# AUX_power_board.net
KiCad netlist of a schematic drawn in EAGLE
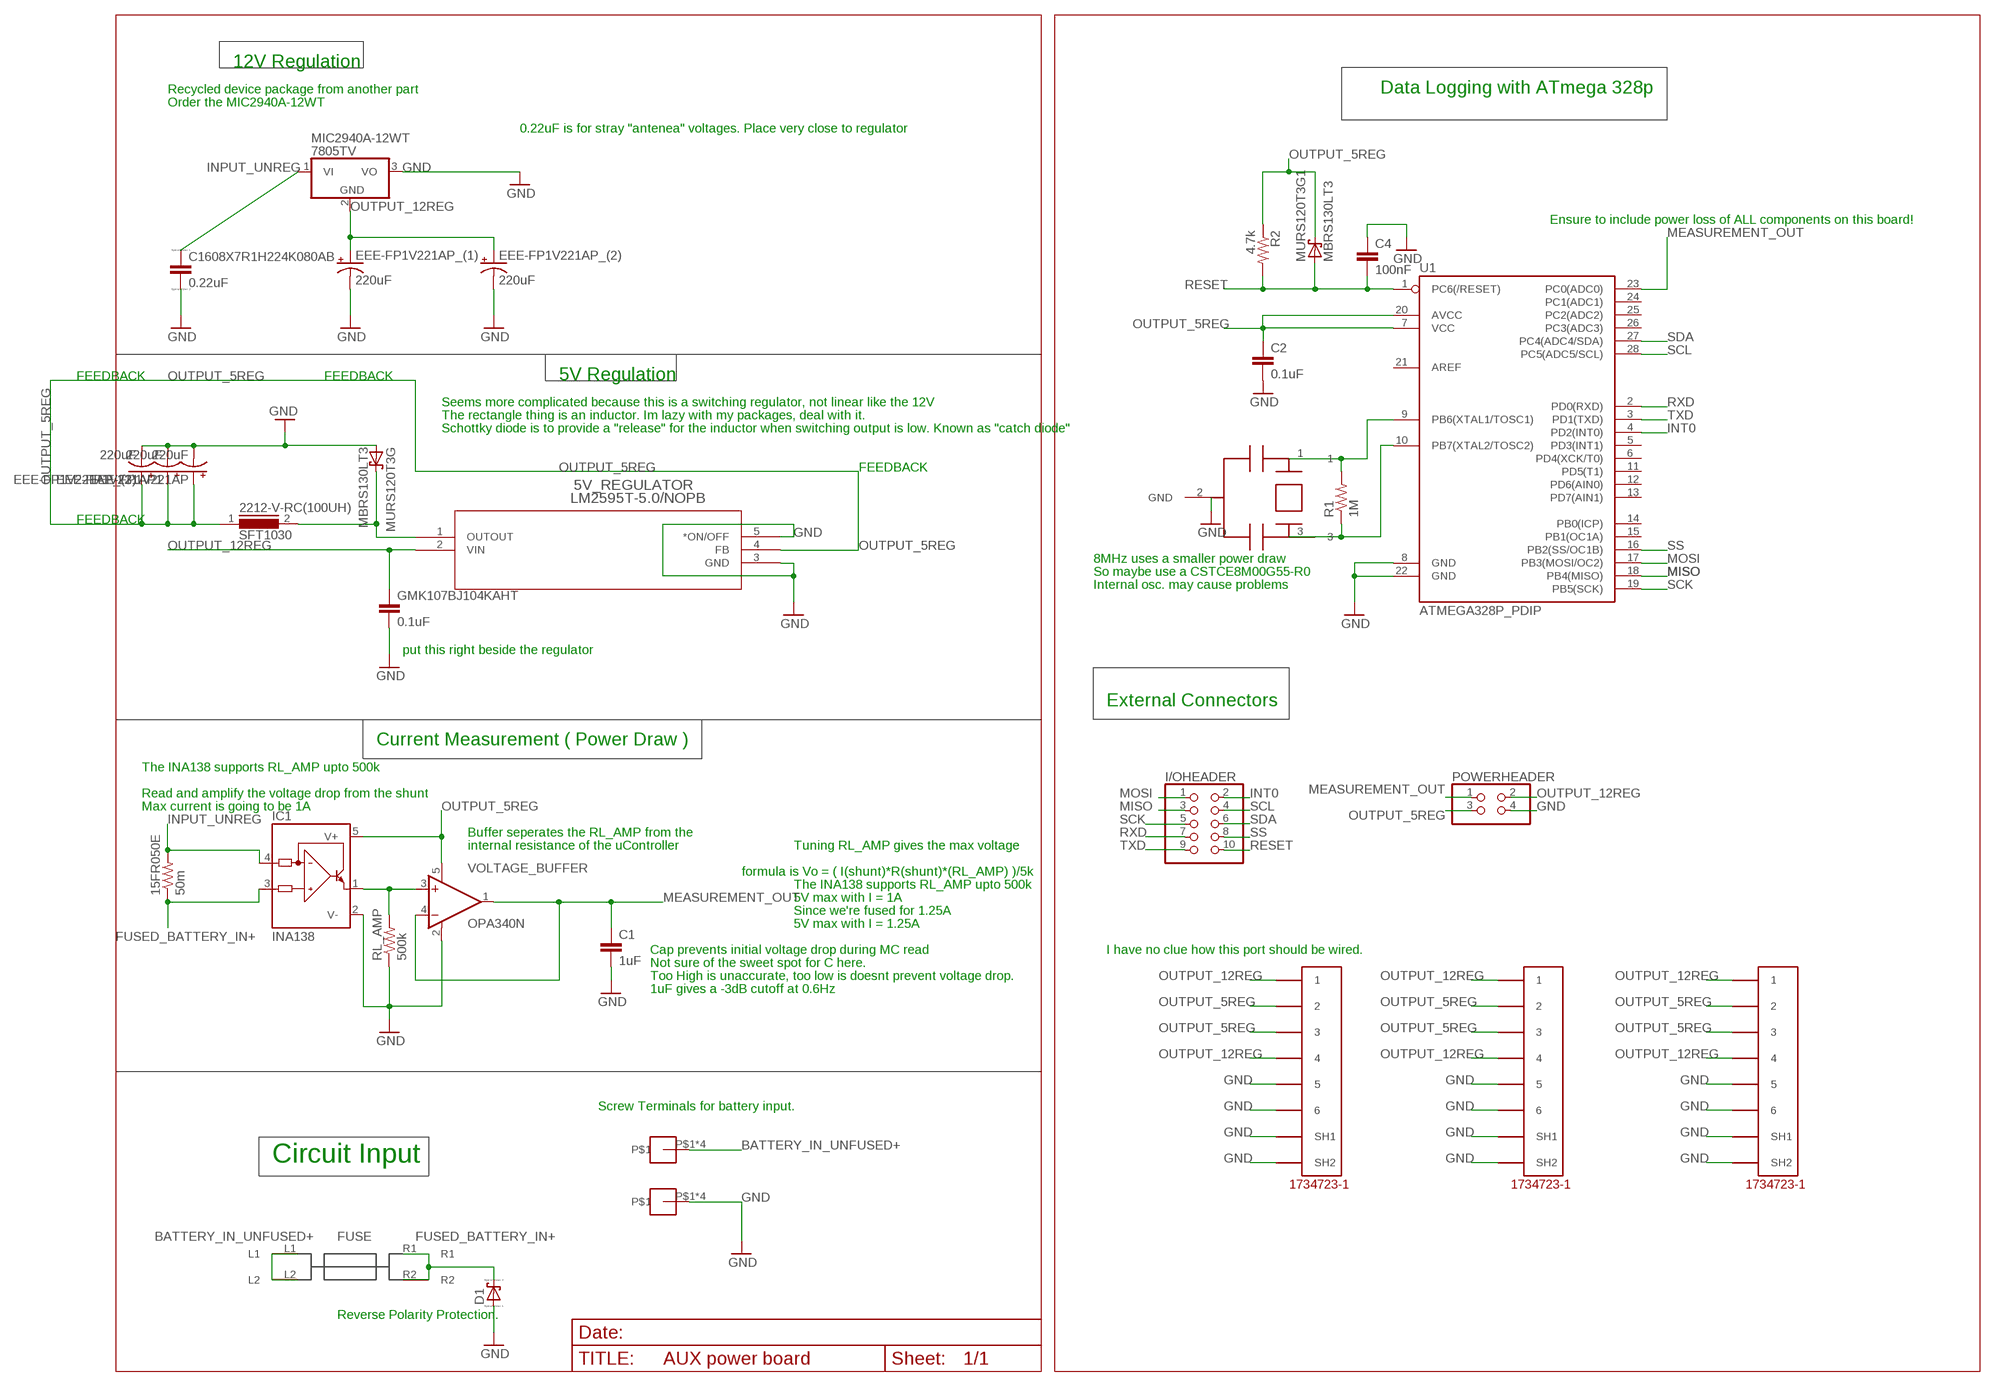
[diagram p0: schematic, sheet 1]

(export (version "E")
  (design (tool "Eeschema 10.0.6"))
  (components
    (comp (ref "5V_REGULATOR")
      (value "LM2595T-5.0/NOPB")
      (footprint "eagle-import:T05D")
      (fields
        (field (name "MANUFACTURER_PART_NUMBER") "LM2595T50")
        (field (name "COPYRIGHT") "Copyright C 2015 Accelerated Designs. All rights reserved")
      )
      (libsource (lib "eagle-import") (part "LM2595T-5.0/NOPB"))
    )
    (comp (ref "15FR050E")
      (value "50m")
      (footprint "eagle-import:0617_22")
      (libsource (lib "eagle-import") (part "resistor_R-US_0617/22"))
    )
    (comp (ref "2212-V-RC(100UH)")
      (value "SFT1030")
      (footprint "eagle-import:SFT1030")
      (libsource (lib "eagle-import") (part "SFT1030"))
    )
    (comp (ref "C1")
      (value "1uF")
      (footprint "eagle-import:C0603")
      (libsource (lib "eagle-import") (part "resistor_C-EUC0603"))
    )
    (comp (ref "C2")
      (value "0.1uF")
      (footprint "eagle-import:C0603")
      (libsource (lib "eagle-import") (part "resistor_C-EUC0603"))
    )
    (comp (ref "C4")
      (value "100nF")
      (footprint "eagle-import:C0603")
      (libsource (lib "eagle-import") (part "C-EUC0603"))
    )
    (comp (ref "C1608X7R1H224K080AB")
      (value "0.22uF")
      (footprint "eagle-import:C0603")
      (libsource (lib "eagle-import") (part "CC0603"))
    )
    (comp (ref "D1")
      (value "SCHOTTKY-DIODESMC")
      (footprint "eagle-import:DIODE_SMC")
      (libsource (lib "eagle-import") (part "SCHOTTKY-DIODESMC"))
    )
    (comp (ref "EEE-FP1V221AP")
      (value "220uF")
      (footprint "eagle-import:175TMP-0808")
      (libsource (lib "eagle-import") (part "CPOL-US175TMP-0808"))
    )
    (comp (ref "EEE-FP1V221AP1")
      (value "220uF")
      (footprint "eagle-import:175TMP-0808")
      (libsource (lib "eagle-import") (part "CPOL-US175TMP-0808"))
    )
    (comp (ref "EEE-FP1V221AP_(1)")
      (value "220uF")
      (footprint "eagle-import:175TMP-0808")
      (libsource (lib "eagle-import") (part "CPOL-US175TMP-0808"))
    )
    (comp (ref "EEE-FP1V221AP_(2)")
      (value "220uF")
      (footprint "eagle-import:175TMP-0808")
      (libsource (lib "eagle-import") (part "CPOL-US175TMP-0808"))
    )
    (comp (ref "EEE-FP1V221AP_(3)")
      (value "220uF")
      (footprint "eagle-import:175TMP-0808")
      (libsource (lib "eagle-import") (part "CPOL-US175TMP-0808"))
    )
    (comp (ref "GMK107BJ104KAHT")
      (value "0.1uF")
      (footprint "eagle-import:C0603")
      (libsource (lib "eagle-import") (part "C-EUC0603"))
    )
    (comp (ref "I/OHEADER")
      (value "PINHD-2X5")
      (footprint "eagle-import:2X05")
      (libsource (lib "eagle-import") (part "PINHD-2X5"))
    )
    (comp (ref "IC1")
      (value "INA138")
      (footprint "eagle-import:SOT23-5")
      (fields (field (name "MF") "TEXAS INSTRUMENTS") (field (name "MPN") "INA138NA/250"))
      (libsource (lib "eagle-import") (part "INA138"))
    )
    (comp (ref "MIC2940A-12WT")
      (value "7805TV")
      (footprint "eagle-import:TO220V")
      (libsource (lib "eagle-import") (part "78TV05"))
    )
    (comp (ref "MINIBLADE")
      (value "3568")
      (footprint "eagle-import:3568")
      (libsource (lib "eagle-import") (part "3568"))
    )
    (comp (ref "MURS120T3G")
      (value "MBRS130LT3")
      (footprint "eagle-import:SMB")
      (libsource (lib "eagle-import") (part "MBRS130LT3"))
    )
    (comp (ref "MURS120T3G1")
      (value "MBRS130LT3")
      (footprint "eagle-import:SMB")
      (libsource (lib "eagle-import") (part "MBRS130LT3"))
    )
    (comp (ref "POWERHEADER")
      (value "PINHD-2X2")
      (footprint "eagle-import:2X02")
      (libsource (lib "eagle-import") (part "PINHD-2X2"))
    )
    (comp (ref "R1")
      (value "1M")
      (footprint "eagle-import:R0603")
      (libsource (lib "eagle-import") (part "R-US_R0603"))
    )
    (comp (ref "R2")
      (value "4.7k")
      (footprint "eagle-import:R0603")
      (libsource (lib "eagle-import") (part "resistor_R-US_R0603"))
    )
    (comp (ref "RL_AMP")
      (value "500k")
      (footprint "eagle-import:R0603")
      (libsource (lib "eagle-import") (part "resistor_R-US_R0603"))
    )
    (comp (ref "U$1")
      (value "CSTCE16M0V53-R0")
      (footprint "eagle-import:RESONATOR")
      (libsource (lib "eagle-import") (part "CSTCE16M0V53-R0"))
    )
    (comp (ref "U$3")
      (value "5555140-6")
      (footprint "eagle-import:1734723-1_RJ11")
      (libsource (lib "eagle-import") (part "5555140-6"))
    )
    (comp (ref "U$4")
      (value "5555140-6")
      (footprint "eagle-import:1734723-1_RJ11")
      (libsource (lib "eagle-import") (part "5555140-6"))
    )
    (comp (ref "U$5")
      (value "5555140-6")
      (footprint "eagle-import:1734723-1_RJ11")
      (libsource (lib "eagle-import") (part "5555140-6"))
    )
    (comp (ref "U$6")
      (value "SCREW-8191")
      (footprint "eagle-import:SCREW-8191")
      (libsource (lib "eagle-import") (part "SCREW-8191"))
    )
    (comp (ref "U$7")
      (value "SCREW-8191")
      (footprint "eagle-import:SCREW-8191")
      (libsource (lib "eagle-import") (part "SCREW-8191"))
    )
    (comp (ref "U1")
      (value "ATMEGA328P_PDIP")
      (footprint "eagle-import:DIL28-3")
      (libsource (lib "eagle-import") (part "ATMEGA328P_PDIP"))
    )
    (comp (ref "VOLTAGE_BUFFER")
      (value "OPA340N")
      (footprint "eagle-import:SOT23-5")
      (fields (field (name "MPN") "OPA340NA/3KG4"))
      (libsource (lib "eagle-import") (part "OPA340N"))
    )
  )
  (nets
    (net (code "1") (name "/BATTERY_IN_UNFUSED+") (class "Default")
      (node (ref "MINIBLADE") (pin "L1") (pinfunction "L1_L1") (pintype "bidirectional"))
      (node (ref "MINIBLADE") (pin "L2") (pinfunction "L2_L2") (pintype "bidirectional"))
      (node (ref "U$6") (pin "P$1") (pinfunction "P$1_P$1") (pintype "bidirectional"))
      (node (ref "U$6") (pin "P$2") (pinfunction "P$1_P$2") (pintype "bidirectional"))
      (node (ref "U$6") (pin "P$3") (pinfunction "P$1_P$3") (pintype "bidirectional"))
      (node (ref "U$6") (pin "P$4") (pinfunction "P$1_P$4") (pintype "bidirectional"))
    )
    (net (code "2") (name "/FUSED_BATTERY_IN+") (class "Default")
      (node (ref "15FR050E") (pin "1") (pinfunction "1_1") (pintype "passive"))
      (node (ref "D1") (pin "C") (pinfunction "A_C") (pintype "passive"))
      (node (ref "IC1") (pin "3") (pinfunction "IN+_3") (pintype "input"))
      (node (ref "MINIBLADE") (pin "R1") (pinfunction "R1_R1") (pintype "bidirectional"))
      (node (ref "MINIBLADE") (pin "R2") (pinfunction "R2_R2") (pintype "bidirectional"))
    )
    (net (code "3") (name "/INPUT_UNREG") (class "Default")
      (node (ref "15FR050E") (pin "2") (pinfunction "2_2") (pintype "passive"))
      (node (ref "C1608X7R1H224K080AB") (pin "1") (pinfunction "1_1") (pintype "passive"))
      (node (ref "IC1") (pin "4") (pinfunction "IN-_4") (pintype "input"))
      (node (ref "MIC2940A-12WT") (pin "1") (pinfunction "VI_1") (pintype "input"))
    )
    (net (code "4") (name "/INT0") (class "Default")
      (node (ref "I/OHEADER") (pin "2") (pinfunction "2_2") (pintype "passive"))
      (node (ref "U1") (pin "4") (pinfunction "PD2(INT0)_4") (pintype "bidirectional"))
    )
    (net (code "5") (name "/MEASUREMENT_OUT") (class "Default")
      (node (ref "C1") (pin "1") (pinfunction "1_1") (pintype "passive"))
      (node (ref "POWERHEADER") (pin "1") (pinfunction "1_1") (pintype "passive"))
      (node (ref "U1") (pin "23") (pinfunction "PC0(ADC0)_23") (pintype "bidirectional"))
      (node (ref "VOLTAGE_BUFFER") (pin "1") (pinfunction "OUT_1") (pintype "output"))
      (node (ref "VOLTAGE_BUFFER") (pin "4") (pinfunction "-IN_4") (pintype "input"))
    )
    (net (code "6") (name "/MISO") (class "Default")
      (node (ref "I/OHEADER") (pin "3") (pinfunction "3_3") (pintype "passive"))
      (node (ref "U1") (pin "18") (pinfunction "PB4(MISO)_18") (pintype "bidirectional"))
    )
    (net (code "7") (name "/MOSI") (class "Default")
      (node (ref "I/OHEADER") (pin "1") (pinfunction "1_1") (pintype "passive"))
      (node (ref "U1") (pin "17") (pinfunction "PB3(MOSI/OC2)_17") (pintype "bidirectional"))
    )
    (net (code "8") (name "/OUTPUT_5REG") (class "Default")
      (node (ref "2212-V-RC(100UH)") (pin "1") (pinfunction "1_1") (pintype "passive"))
      (node (ref "5V_REGULATOR") (pin "4") (pinfunction "FB_4") (pintype "passive"))
      (node (ref "C2") (pin "1") (pinfunction "1_1") (pintype "passive"))
      (node (ref "EEE-FP1V221AP") (pin "+") (pinfunction "+_+") (pintype "passive"))
      (node (ref "EEE-FP1V221AP1") (pin "+") (pinfunction "+_+") (pintype "passive"))
      (node (ref "EEE-FP1V221AP_(3)") (pin "+") (pinfunction "+_+") (pintype "passive"))
      (node (ref "IC1") (pin "5") (pinfunction "V+_5") (pintype "power_in"))
      (node (ref "MURS120T3G1") (pin "C") (pinfunction "C_C") (pintype "passive"))
      (node (ref "POWERHEADER") (pin "3") (pinfunction "3_3") (pintype "passive"))
      (node (ref "R2") (pin "1") (pinfunction "1_1") (pintype "passive"))
      (node (ref "U$3") (pin "2") (pinfunction "2_2") (pintype "bidirectional"))
      (node (ref "U$3") (pin "3") (pinfunction "3_3") (pintype "bidirectional"))
      (node (ref "U$4") (pin "2") (pinfunction "2_2") (pintype "bidirectional"))
      (node (ref "U$4") (pin "3") (pinfunction "3_3") (pintype "bidirectional"))
      (node (ref "U$5") (pin "2") (pinfunction "2_2") (pintype "bidirectional"))
      (node (ref "U$5") (pin "3") (pinfunction "3_3") (pintype "bidirectional"))
      (node (ref "U1") (pin "20") (pinfunction "AVCC_20") (pintype "bidirectional"))
      (node (ref "U1") (pin "7") (pinfunction "VCC_7") (pintype "bidirectional"))
      (node (ref "VOLTAGE_BUFFER") (pin "5") (pinfunction "V+_5") (pintype "power_in"))
    )
    (net (code "9") (name "/OUTPUT_12REG") (class "Default")
      (node (ref "5V_REGULATOR") (pin "2") (pinfunction "VIN_2") (pintype "input"))
      (node (ref "EEE-FP1V221AP_(1)") (pin "+") (pinfunction "+_+") (pintype "passive"))
      (node (ref "EEE-FP1V221AP_(2)") (pin "+") (pinfunction "+_+") (pintype "passive"))
      (node (ref "GMK107BJ104KAHT") (pin "1") (pinfunction "1_1") (pintype "passive"))
      (node (ref "MIC2940A-12WT") (pin "2") (pinfunction "GND_2") (pintype "passive"))
      (node (ref "POWERHEADER") (pin "2") (pinfunction "2_2") (pintype "passive"))
      (node (ref "U$3") (pin "1") (pinfunction "1_1") (pintype "bidirectional"))
      (node (ref "U$3") (pin "4") (pinfunction "4_4") (pintype "bidirectional"))
      (node (ref "U$4") (pin "1") (pinfunction "1_1") (pintype "bidirectional"))
      (node (ref "U$4") (pin "4") (pinfunction "4_4") (pintype "bidirectional"))
      (node (ref "U$5") (pin "1") (pinfunction "1_1") (pintype "bidirectional"))
      (node (ref "U$5") (pin "4") (pinfunction "4_4") (pintype "bidirectional"))
    )
    (net (code "10") (name "/RESET") (class "Default")
      (node (ref "C4") (pin "2") (pinfunction "2_2") (pintype "passive"))
      (node (ref "I/OHEADER") (pin "10") (pinfunction "10_10") (pintype "passive"))
      (node (ref "MURS120T3G1") (pin "A") (pinfunction "A_A") (pintype "passive"))
      (node (ref "R2") (pin "2") (pinfunction "2_2") (pintype "passive"))
      (node (ref "U1") (pin "1") (pinfunction "PC6(/RESET)_1") (pintype "bidirectional"))
    )
    (net (code "11") (name "/RXD") (class "Default")
      (node (ref "I/OHEADER") (pin "7") (pinfunction "7_7") (pintype "passive"))
      (node (ref "U1") (pin "2") (pinfunction "PD0(RXD)_2") (pintype "bidirectional"))
    )
    (net (code "12") (name "/SCK") (class "Default")
      (node (ref "I/OHEADER") (pin "5") (pinfunction "5_5") (pintype "passive"))
      (node (ref "U1") (pin "19") (pinfunction "PB5(SCK)_19") (pintype "bidirectional"))
    )
    (net (code "13") (name "/SCL") (class "Default")
      (node (ref "I/OHEADER") (pin "4") (pinfunction "4_4") (pintype "passive"))
      (node (ref "U1") (pin "28") (pinfunction "PC5(ADC5/SCL)_28") (pintype "bidirectional"))
    )
    (net (code "14") (name "/SDA") (class "Default")
      (node (ref "I/OHEADER") (pin "6") (pinfunction "6_6") (pintype "passive"))
      (node (ref "U1") (pin "27") (pinfunction "PC4(ADC4/SDA)_27") (pintype "bidirectional"))
    )
    (net (code "15") (name "/SS") (class "Default")
      (node (ref "I/OHEADER") (pin "8") (pinfunction "8_8") (pintype "passive"))
      (node (ref "U1") (pin "16") (pinfunction "PB2(SS/OC1B)_16") (pintype "bidirectional"))
    )
    (net (code "16") (name "/TXD") (class "Default")
      (node (ref "I/OHEADER") (pin "9") (pinfunction "9_9") (pintype "passive"))
      (node (ref "U1") (pin "3") (pinfunction "PD1(TXD)_3") (pintype "bidirectional"))
    )
    (net (code "17") (name "GND") (class "Default")
      (node (ref "5V_REGULATOR") (pin "3") (pinfunction "GND_3") (pintype "passive"))
      (node (ref "5V_REGULATOR") (pin "5") (pinfunction "*ON/OFF_5") (pintype "passive"))
      (node (ref "C1") (pin "2") (pinfunction "2_2") (pintype "passive"))
      (node (ref "C1608X7R1H224K080AB") (pin "2") (pinfunction "2_2") (pintype "passive"))
      (node (ref "C2") (pin "2") (pinfunction "2_2") (pintype "passive"))
      (node (ref "C4") (pin "1") (pinfunction "1_1") (pintype "passive"))
      (node (ref "D1") (pin "A") (pinfunction "C_A") (pintype "passive"))
      (node (ref "EEE-FP1V221AP") (pin "-") (pinfunction "-_-") (pintype "passive"))
      (node (ref "EEE-FP1V221AP1") (pin "-") (pinfunction "-_-") (pintype "passive"))
      (node (ref "EEE-FP1V221AP_(1)") (pin "-") (pinfunction "-_-") (pintype "passive"))
      (node (ref "EEE-FP1V221AP_(2)") (pin "-") (pinfunction "-_-") (pintype "passive"))
      (node (ref "EEE-FP1V221AP_(3)") (pin "-") (pinfunction "-_-") (pintype "passive"))
      (node (ref "GMK107BJ104KAHT") (pin "2") (pinfunction "2_2") (pintype "passive"))
      (node (ref "IC1") (pin "2") (pinfunction "V-_2") (pintype "power_in"))
      (node (ref "MIC2940A-12WT") (pin "3") (pinfunction "VO_3") (pintype "passive"))
      (node (ref "MURS120T3G") (pin "A") (pinfunction "A_A") (pintype "passive"))
      (node (ref "POWERHEADER") (pin "4") (pinfunction "4_4") (pintype "passive"))
      (node (ref "RL_AMP") (pin "1") (pinfunction "1_1") (pintype "passive"))
      (node (ref "U$1") (pin "2") (pinfunction "GND_2") (pintype "bidirectional"))
      (node (ref "U$3") (pin "5") (pinfunction "5_5") (pintype "bidirectional"))
      (node (ref "U$3") (pin "6") (pinfunction "6_6") (pintype "bidirectional"))
      (node (ref "U$3") (pin "SH1") (pinfunction "SH1_SH1") (pintype "bidirectional"))
      (node (ref "U$3") (pin "SH2") (pinfunction "SH2_SH2") (pintype "bidirectional"))
      (node (ref "U$4") (pin "5") (pinfunction "5_5") (pintype "bidirectional"))
      (node (ref "U$4") (pin "6") (pinfunction "6_6") (pintype "bidirectional"))
      (node (ref "U$4") (pin "SH1") (pinfunction "SH1_SH1") (pintype "bidirectional"))
      (node (ref "U$4") (pin "SH2") (pinfunction "SH2_SH2") (pintype "bidirectional"))
      (node (ref "U$5") (pin "5") (pinfunction "5_5") (pintype "bidirectional"))
      (node (ref "U$5") (pin "6") (pinfunction "6_6") (pintype "bidirectional"))
      (node (ref "U$5") (pin "SH1") (pinfunction "SH1_SH1") (pintype "bidirectional"))
      (node (ref "U$5") (pin "SH2") (pinfunction "SH2_SH2") (pintype "bidirectional"))
      (node (ref "U$7") (pin "P$1") (pinfunction "P$1_P$1") (pintype "bidirectional"))
      (node (ref "U$7") (pin "P$2") (pinfunction "P$1_P$2") (pintype "bidirectional"))
      (node (ref "U$7") (pin "P$3") (pinfunction "P$1_P$3") (pintype "bidirectional"))
      (node (ref "U$7") (pin "P$4") (pinfunction "P$1_P$4") (pintype "bidirectional"))
      (node (ref "U1") (pin "22") (pinfunction "GND_22") (pintype "bidirectional"))
      (node (ref "U1") (pin "8") (pinfunction "GND_8") (pintype "bidirectional"))
      (node (ref "VOLTAGE_BUFFER") (pin "2") (pinfunction "V-_2") (pintype "power_in"))
    )
    (net (code "18") (name "Net-(5V_REGULATOR-OUTOUT)") (class "Default")
      (node (ref "2212-V-RC(100UH)") (pin "2") (pinfunction "2_2") (pintype "passive"))
      (node (ref "5V_REGULATOR") (pin "1") (pinfunction "OUTOUT_1") (pintype "output"))
      (node (ref "MURS120T3G") (pin "C") (pinfunction "C_C") (pintype "passive"))
    )
    (net (code "19") (name "Net-(IC1-OUT)") (class "Default")
      (node (ref "IC1") (pin "1") (pinfunction "OUT_1") (pintype "output"))
      (node (ref "RL_AMP") (pin "2") (pinfunction "2_2") (pintype "passive"))
      (node (ref "VOLTAGE_BUFFER") (pin "3") (pinfunction "+IN_3") (pintype "input"))
    )
    (net (code "20") (name "Net-(U1-PB6(XTAL1{slash}TOSC1))") (class "Default")
      (node (ref "R1") (pin "2") (pinfunction "2_2") (pintype "passive"))
      (node (ref "U$1") (pin "1") (pinfunction "1_1") (pintype "bidirectional"))
      (node (ref "U1") (pin "9") (pinfunction "PB6(XTAL1/TOSC1)_9") (pintype "bidirectional"))
    )
    (net (code "21") (name "Net-(U1-PB7(XTAL2{slash}TOSC2))") (class "Default")
      (node (ref "R1") (pin "1") (pinfunction "1_1") (pintype "passive"))
      (node (ref "U$1") (pin "3") (pinfunction "3_3") (pintype "bidirectional"))
      (node (ref "U1") (pin "10") (pinfunction "PB7(XTAL2/TOSC2)_10") (pintype "bidirectional"))
    )
    (net (code "22") (name "unconnected-(U1-AREF-Pad21)") (class "Default")
      (node (ref "U1") (pin "21") (pinfunction "AREF_21") (pintype "bidirectional"))
    )
    (net (code "23") (name "unconnected-(U1-PB0(ICP)-Pad14)") (class "Default")
      (node (ref "U1") (pin "14") (pinfunction "PB0(ICP)_14") (pintype "bidirectional"))
    )
    (net (code "24") (name "unconnected-(U1-PB1(OC1A)-Pad15)") (class "Default")
      (node (ref "U1") (pin "15") (pinfunction "PB1(OC1A)_15") (pintype "bidirectional"))
    )
    (net (code "25") (name "unconnected-(U1-PC1(ADC1)-Pad24)") (class "Default")
      (node (ref "U1") (pin "24") (pinfunction "PC1(ADC1)_24") (pintype "bidirectional"))
    )
    (net (code "26") (name "unconnected-(U1-PC2(ADC2)-Pad25)") (class "Default")
      (node (ref "U1") (pin "25") (pinfunction "PC2(ADC2)_25") (pintype "bidirectional"))
    )
    (net (code "27") (name "unconnected-(U1-PC3(ADC3)-Pad26)") (class "Default")
      (node (ref "U1") (pin "26") (pinfunction "PC3(ADC3)_26") (pintype "bidirectional"))
    )
    (net (code "28") (name "unconnected-(U1-PD3(INT1)-Pad5)") (class "Default")
      (node (ref "U1") (pin "5") (pinfunction "PD3(INT1)_5") (pintype "bidirectional"))
    )
    (net (code "29") (name "unconnected-(U1-PD4(XCK{slash}T0)-Pad6)") (class "Default")
      (node (ref "U1") (pin "6") (pinfunction "PD4(XCK/T0)_6") (pintype "bidirectional"))
    )
    (net (code "30") (name "unconnected-(U1-PD5(T1)-Pad11)") (class "Default")
      (node (ref "U1") (pin "11") (pinfunction "PD5(T1)_11") (pintype "bidirectional"))
    )
    (net (code "31") (name "unconnected-(U1-PD6(AIN0)-Pad12)") (class "Default")
      (node (ref "U1") (pin "12") (pinfunction "PD6(AIN0)_12") (pintype "bidirectional"))
    )
    (net (code "32") (name "unconnected-(U1-PD7(AIN1)-Pad13)") (class "Default")
      (node (ref "U1") (pin "13") (pinfunction "PD7(AIN1)_13") (pintype "bidirectional"))
    )
  )
)
